# Thermometers.net
KiCad netlist of a schematic drawn in Altium Designer
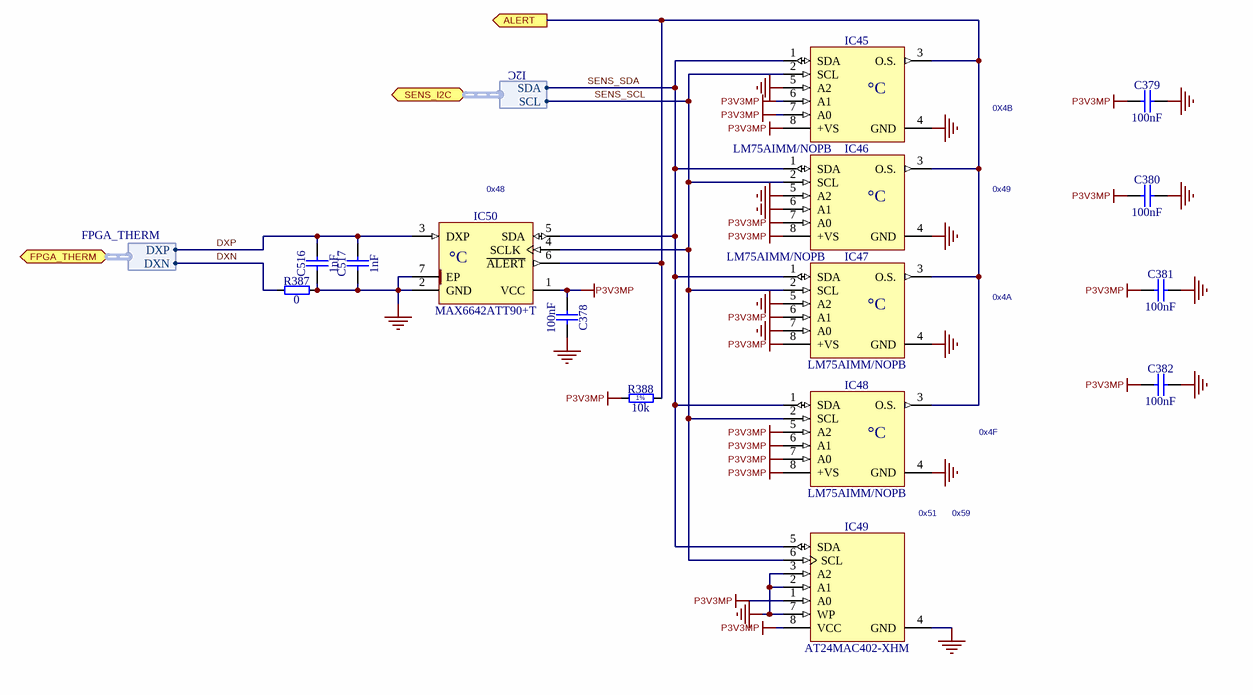
[diagram p0: Thermometers.SchDoc]

(export (version "E")
  (design (tool "Eeschema 10.0.6"))
  (components
    (comp (ref "C378")
      (value "100nF")
      (footprint "CAPC0603X33N")
      (description "Non-polarised capacitor")
      (fields
        (field (name "MANUFACTURER PART NUMBER") "CC0201_100NF_6.3V_10%_X5R")
        (field (name "MANUFACTURER") "GENERIC")
        (field (name "AUTHOR") "CERN DEM JLC")
      )
      (libsource (lib "Capacitors") (part "Capacitor - non polarized"))
    )
    (comp (ref "C379")
      (value "100nF")
      (footprint "CAPC0603X33N")
      (description "Non-polarised capacitor")
      (fields
        (field (name "MANUFACTURER PART NUMBER") "CC0201_100NF_6.3V_10%_X5R")
        (field (name "MANUFACTURER") "GENERIC")
        (field (name "AUTHOR") "CERN DEM JLC")
      )
      (libsource (lib "Capacitors") (part "Capacitor - non polarized"))
    )
    (comp (ref "C380")
      (value "100nF")
      (footprint "CAPC0603X33N")
      (description "Non-polarised capacitor")
      (fields
        (field (name "MANUFACTURER PART NUMBER") "CC0201_100NF_6.3V_10%_X5R")
        (field (name "MANUFACTURER") "GENERIC")
        (field (name "AUTHOR") "CERN DEM JLC")
      )
      (libsource (lib "Capacitors") (part "Capacitor - non polarized"))
    )
    (comp (ref "C381")
      (value "100nF")
      (footprint "CAPC0603X33N")
      (description "Non-polarised capacitor")
      (fields
        (field (name "MANUFACTURER PART NUMBER") "CC0201_100NF_6.3V_10%_X5R")
        (field (name "MANUFACTURER") "GENERIC")
        (field (name "AUTHOR") "CERN DEM JLC")
      )
      (libsource (lib "Capacitors") (part "Capacitor - non polarized"))
    )
    (comp (ref "C382")
      (value "100nF")
      (footprint "CAPC0603X33N")
      (description "Non-polarised capacitor")
      (fields
        (field (name "MANUFACTURER PART NUMBER") "CC0201_100NF_6.3V_10%_X5R")
        (field (name "MANUFACTURER") "GENERIC")
        (field (name "AUTHOR") "CERN DEM JLC")
      )
      (libsource (lib "Capacitors") (part "Capacitor - non polarized"))
    )
    (comp (ref "C516")
      (value "1nF")
      (footprint "CAPC1005X55N")
      (description "Non-polarised capacitor")
      (fields
        (field (name "MANUFACTURER PART NUMBER") "CC0402_1NF_50V_10%_X7R")
        (field (name "MANUFACTURER") "GENERIC")
        (field (name "AUTHOR") "CERN DEM JLC")
      )
      (libsource (lib "Capacitors") (part "Capacitor - non polarized"))
    )
    (comp (ref "C517")
      (value "1nF")
      (footprint "CAPC1005X55N")
      (description "Non-polarised capacitor")
      (fields
        (field (name "MANUFACTURER PART NUMBER") "CC0402_1NF_50V_10%_X7R")
        (field (name "MANUFACTURER") "GENERIC")
        (field (name "AUTHOR") "CERN DEM JLC")
      )
      (libsource (lib "Capacitors") (part "Capacitor - non polarized"))
    )
    (comp (ref "IC45")
      (value "LM75AIMM/NOPB")
      (footprint "SOP65P490X109-8N")
      (description "Digital Temperature Sensor and Thermal Watchdog with Two-Wire Interface")
      (fields (field (name "MANUFACTURER") "TEXAS INSTRUMENTS") (field (name "AUTHOR") "CERN DEM JLC"))
      (libsource (lib "ICs And Semiconductors") (part "LM75"))
    )
    (comp (ref "IC46")
      (value "LM75AIMM/NOPB")
      (footprint "SOP65P490X109-8N")
      (description "Digital Temperature Sensor and Thermal Watchdog with Two-Wire Interface")
      (fields (field (name "MANUFACTURER") "TEXAS INSTRUMENTS") (field (name "AUTHOR") "CERN DEM JLC"))
      (libsource (lib "ICs And Semiconductors") (part "LM75"))
    )
    (comp (ref "IC47")
      (value "LM75AIMM/NOPB")
      (footprint "SOP65P490X109-8N")
      (description "Digital Temperature Sensor and Thermal Watchdog with Two-Wire Interface")
      (fields (field (name "MANUFACTURER") "TEXAS INSTRUMENTS") (field (name "AUTHOR") "CERN DEM JLC"))
      (libsource (lib "ICs And Semiconductors") (part "LM75"))
    )
    (comp (ref "IC48")
      (value "LM75AIMM/NOPB")
      (footprint "SOP65P490X109-8N")
      (description "Digital Temperature Sensor and Thermal Watchdog with Two-Wire Interface")
      (fields (field (name "MANUFACTURER") "TEXAS INSTRUMENTS") (field (name "AUTHOR") "CERN DEM JLC"))
      (libsource (lib "ICs And Semiconductors") (part "LM75"))
    )
    (comp (ref "IC49")
      (value "AT24MAC402-XHM")
      (footprint "SOP65P640X120-8N")
      (description "1.7V to 5.5V, I2C-Compatible (2-wire) 2-Kbit (256 x 8) Serial EEPROM")
      (fields (field (name "MANUFACTURER") "ATMEL") (field (name "AUTHOR") "CERN DEM MR"))
      (libsource (lib "ICs And Semiconductors") (part "AT24MAC402-XHM"))
    )
    (comp (ref "IC50")
      (value "MAX6642ATT90+T")
      (footprint "SON95P300X300X80-7N-R160X240")
      (description "±1°C, SMBus-Compatible Remote/Local Temperature Sensor with Overtemperature Alarm")
      (fields (field (name "MANUFACTURER") "MAXIM") (field (name "AUTHOR") "CERN DEM JLC"))
      (libsource (lib "ICs And Semiconductors") (part "MAX6642ATT"))
    )
    (comp (ref "R387")
      (value "0")
      (footprint "RESC1005X40N")
      (description "Resistor")
      (fields
        (field (name "MANUFACTURER PART NUMBER") "R0402_0R_JUMPER")
        (field (name "MANUFACTURER") "GENERIC")
        (field (name "AUTHOR") "CERN DEM JLC")
      )
      (libsource (lib "Resistors") (part "Resistor"))
    )
    (comp (ref "R388")
      (value "10k")
      (footprint "RESC1005X40N")
      (description "Resistor - 1%")
      (fields
        (field (name "MANUFACTURER PART NUMBER") "R0402_10K_1%_0.0625W_100PPM")
        (field (name "MANUFACTURER") "GENERIC")
        (field (name "AUTHOR") "CERN DEM JLC")
      )
      (libsource (lib "Resistors") (part "Resistor - 1%"))
    )
  )
  (nets
    (net (code "3") (name "/ALERT") (class "Default")
      (node (ref "IC45") (pin "3") (pinfunction "O.S._3") (pintype "output"))
      (node (ref "IC46") (pin "3") (pinfunction "O.S._3") (pintype "output"))
      (node (ref "IC47") (pin "3") (pinfunction "O.S._3") (pintype "output"))
      (node (ref "IC48") (pin "3") (pinfunction "O.S._3") (pintype "output"))
      (node (ref "IC50") (pin "6") (pinfunction "~{ALERT}_6") (pintype "output"))
      (node (ref "R388") (pin "2") (pinfunction "2_2") (pintype "passive"))
    )
    (net (code "4") (name "/DXN") (class "Default")
      (node (ref "R387") (pin "1") (pinfunction "1_1") (pintype "passive"))
    )
    (net (code "5") (name "/DXP") (class "Default")
      (node (ref "C516") (pin "2") (pinfunction "2_2") (pintype "passive"))
      (node (ref "C517") (pin "2") (pinfunction "2_2") (pintype "passive"))
      (node (ref "IC50") (pin "3") (pinfunction "DXP_3") (pintype "input"))
    )
    (net (code "6") (name "/SENS_SCL") (class "Default")
      (node (ref "IC45") (pin "2") (pinfunction "SCL_2") (pintype "input"))
      (node (ref "IC46") (pin "2") (pinfunction "SCL_2") (pintype "input"))
      (node (ref "IC47") (pin "2") (pinfunction "SCL_2") (pintype "input"))
      (node (ref "IC48") (pin "2") (pinfunction "SCL_2") (pintype "input"))
      (node (ref "IC49") (pin "6") (pinfunction "SCL_6") (pintype "input"))
      (node (ref "IC50") (pin "4") (pinfunction "SCLK_4") (pintype "input"))
    )
    (net (code "7") (name "/SENS_SDA") (class "Default")
      (node (ref "IC45") (pin "1") (pinfunction "SDA_1") (pintype "bidirectional"))
      (node (ref "IC46") (pin "1") (pinfunction "SDA_1") (pintype "bidirectional"))
      (node (ref "IC47") (pin "1") (pinfunction "SDA_1") (pintype "bidirectional"))
      (node (ref "IC48") (pin "1") (pinfunction "SDA_1") (pintype "bidirectional"))
      (node (ref "IC49") (pin "5") (pinfunction "SDA_5") (pintype "bidirectional"))
      (node (ref "IC50") (pin "5") (pinfunction "SDA_5") (pintype "bidirectional"))
    )
    (net (code "10") (name "GND") (class "Default")
      (node (ref "C378") (pin "1") (pinfunction "1_1") (pintype "passive"))
      (node (ref "C379") (pin "2") (pinfunction "2_2") (pintype "passive"))
      (node (ref "C380") (pin "2") (pinfunction "2_2") (pintype "passive"))
      (node (ref "C381") (pin "2") (pinfunction "2_2") (pintype "passive"))
      (node (ref "C382") (pin "2") (pinfunction "2_2") (pintype "passive"))
      (node (ref "C516") (pin "1") (pinfunction "1_1") (pintype "passive"))
      (node (ref "C517") (pin "1") (pinfunction "1_1") (pintype "passive"))
      (node (ref "IC45") (pin "4") (pinfunction "GND_4") (pintype "power_in"))
      (node (ref "IC45") (pin "5") (pinfunction "A2_5") (pintype "input"))
      (node (ref "IC46") (pin "4") (pinfunction "GND_4") (pintype "power_in"))
      (node (ref "IC46") (pin "5") (pinfunction "A2_5") (pintype "input"))
      (node (ref "IC46") (pin "6") (pinfunction "A1_6") (pintype "input"))
      (node (ref "IC47") (pin "4") (pinfunction "GND_4") (pintype "power_in"))
      (node (ref "IC47") (pin "5") (pinfunction "A2_5") (pintype "input"))
      (node (ref "IC47") (pin "7") (pinfunction "A0_7") (pintype "input"))
      (node (ref "IC48") (pin "4") (pinfunction "GND_4") (pintype "power_in"))
      (node (ref "IC49") (pin "2") (pinfunction "A1_2") (pintype "input"))
      (node (ref "IC49") (pin "3") (pinfunction "A2_3") (pintype "input"))
      (node (ref "IC49") (pin "4") (pinfunction "GND_4") (pintype "power_in"))
      (node (ref "IC49") (pin "7") (pinfunction "WP_7") (pintype "input"))
      (node (ref "IC50") (pin "2") (pinfunction "GND_2") (pintype "power_in"))
      (node (ref "IC50") (pin "7") (pinfunction "EP_7") (pintype "power_in"))
      (node (ref "R387") (pin "2") (pinfunction "2_2") (pintype "passive"))
    )
    (net (code "11") (name "P3V3MP") (class "Default")
      (node (ref "C378") (pin "2") (pinfunction "2_2") (pintype "passive"))
      (node (ref "C379") (pin "1") (pinfunction "1_1") (pintype "passive"))
      (node (ref "C380") (pin "1") (pinfunction "1_1") (pintype "passive"))
      (node (ref "C381") (pin "1") (pinfunction "1_1") (pintype "passive"))
      (node (ref "C382") (pin "1") (pinfunction "1_1") (pintype "passive"))
      (node (ref "IC45") (pin "6") (pinfunction "A1_6") (pintype "input"))
      (node (ref "IC45") (pin "7") (pinfunction "A0_7") (pintype "input"))
      (node (ref "IC45") (pin "8") (pinfunction "+VS_8") (pintype "power_in"))
      (node (ref "IC46") (pin "7") (pinfunction "A0_7") (pintype "input"))
      (node (ref "IC46") (pin "8") (pinfunction "+VS_8") (pintype "power_in"))
      (node (ref "IC47") (pin "6") (pinfunction "A1_6") (pintype "input"))
      (node (ref "IC47") (pin "8") (pinfunction "+VS_8") (pintype "power_in"))
      (node (ref "IC48") (pin "5") (pinfunction "A2_5") (pintype "input"))
      (node (ref "IC48") (pin "6") (pinfunction "A1_6") (pintype "input"))
      (node (ref "IC48") (pin "7") (pinfunction "A0_7") (pintype "input"))
      (node (ref "IC48") (pin "8") (pinfunction "+VS_8") (pintype "power_in"))
      (node (ref "IC49") (pin "1") (pinfunction "A0_1") (pintype "input"))
      (node (ref "IC49") (pin "8") (pinfunction "VCC_8") (pintype "power_in"))
      (node (ref "IC50") (pin "1") (pinfunction "VCC_1") (pintype "power_in"))
      (node (ref "R388") (pin "1") (pinfunction "1_1") (pintype "passive"))
    )
  )
)
